# BCN3D.net
KiCad netlist of a schematic drawn in EAGLE
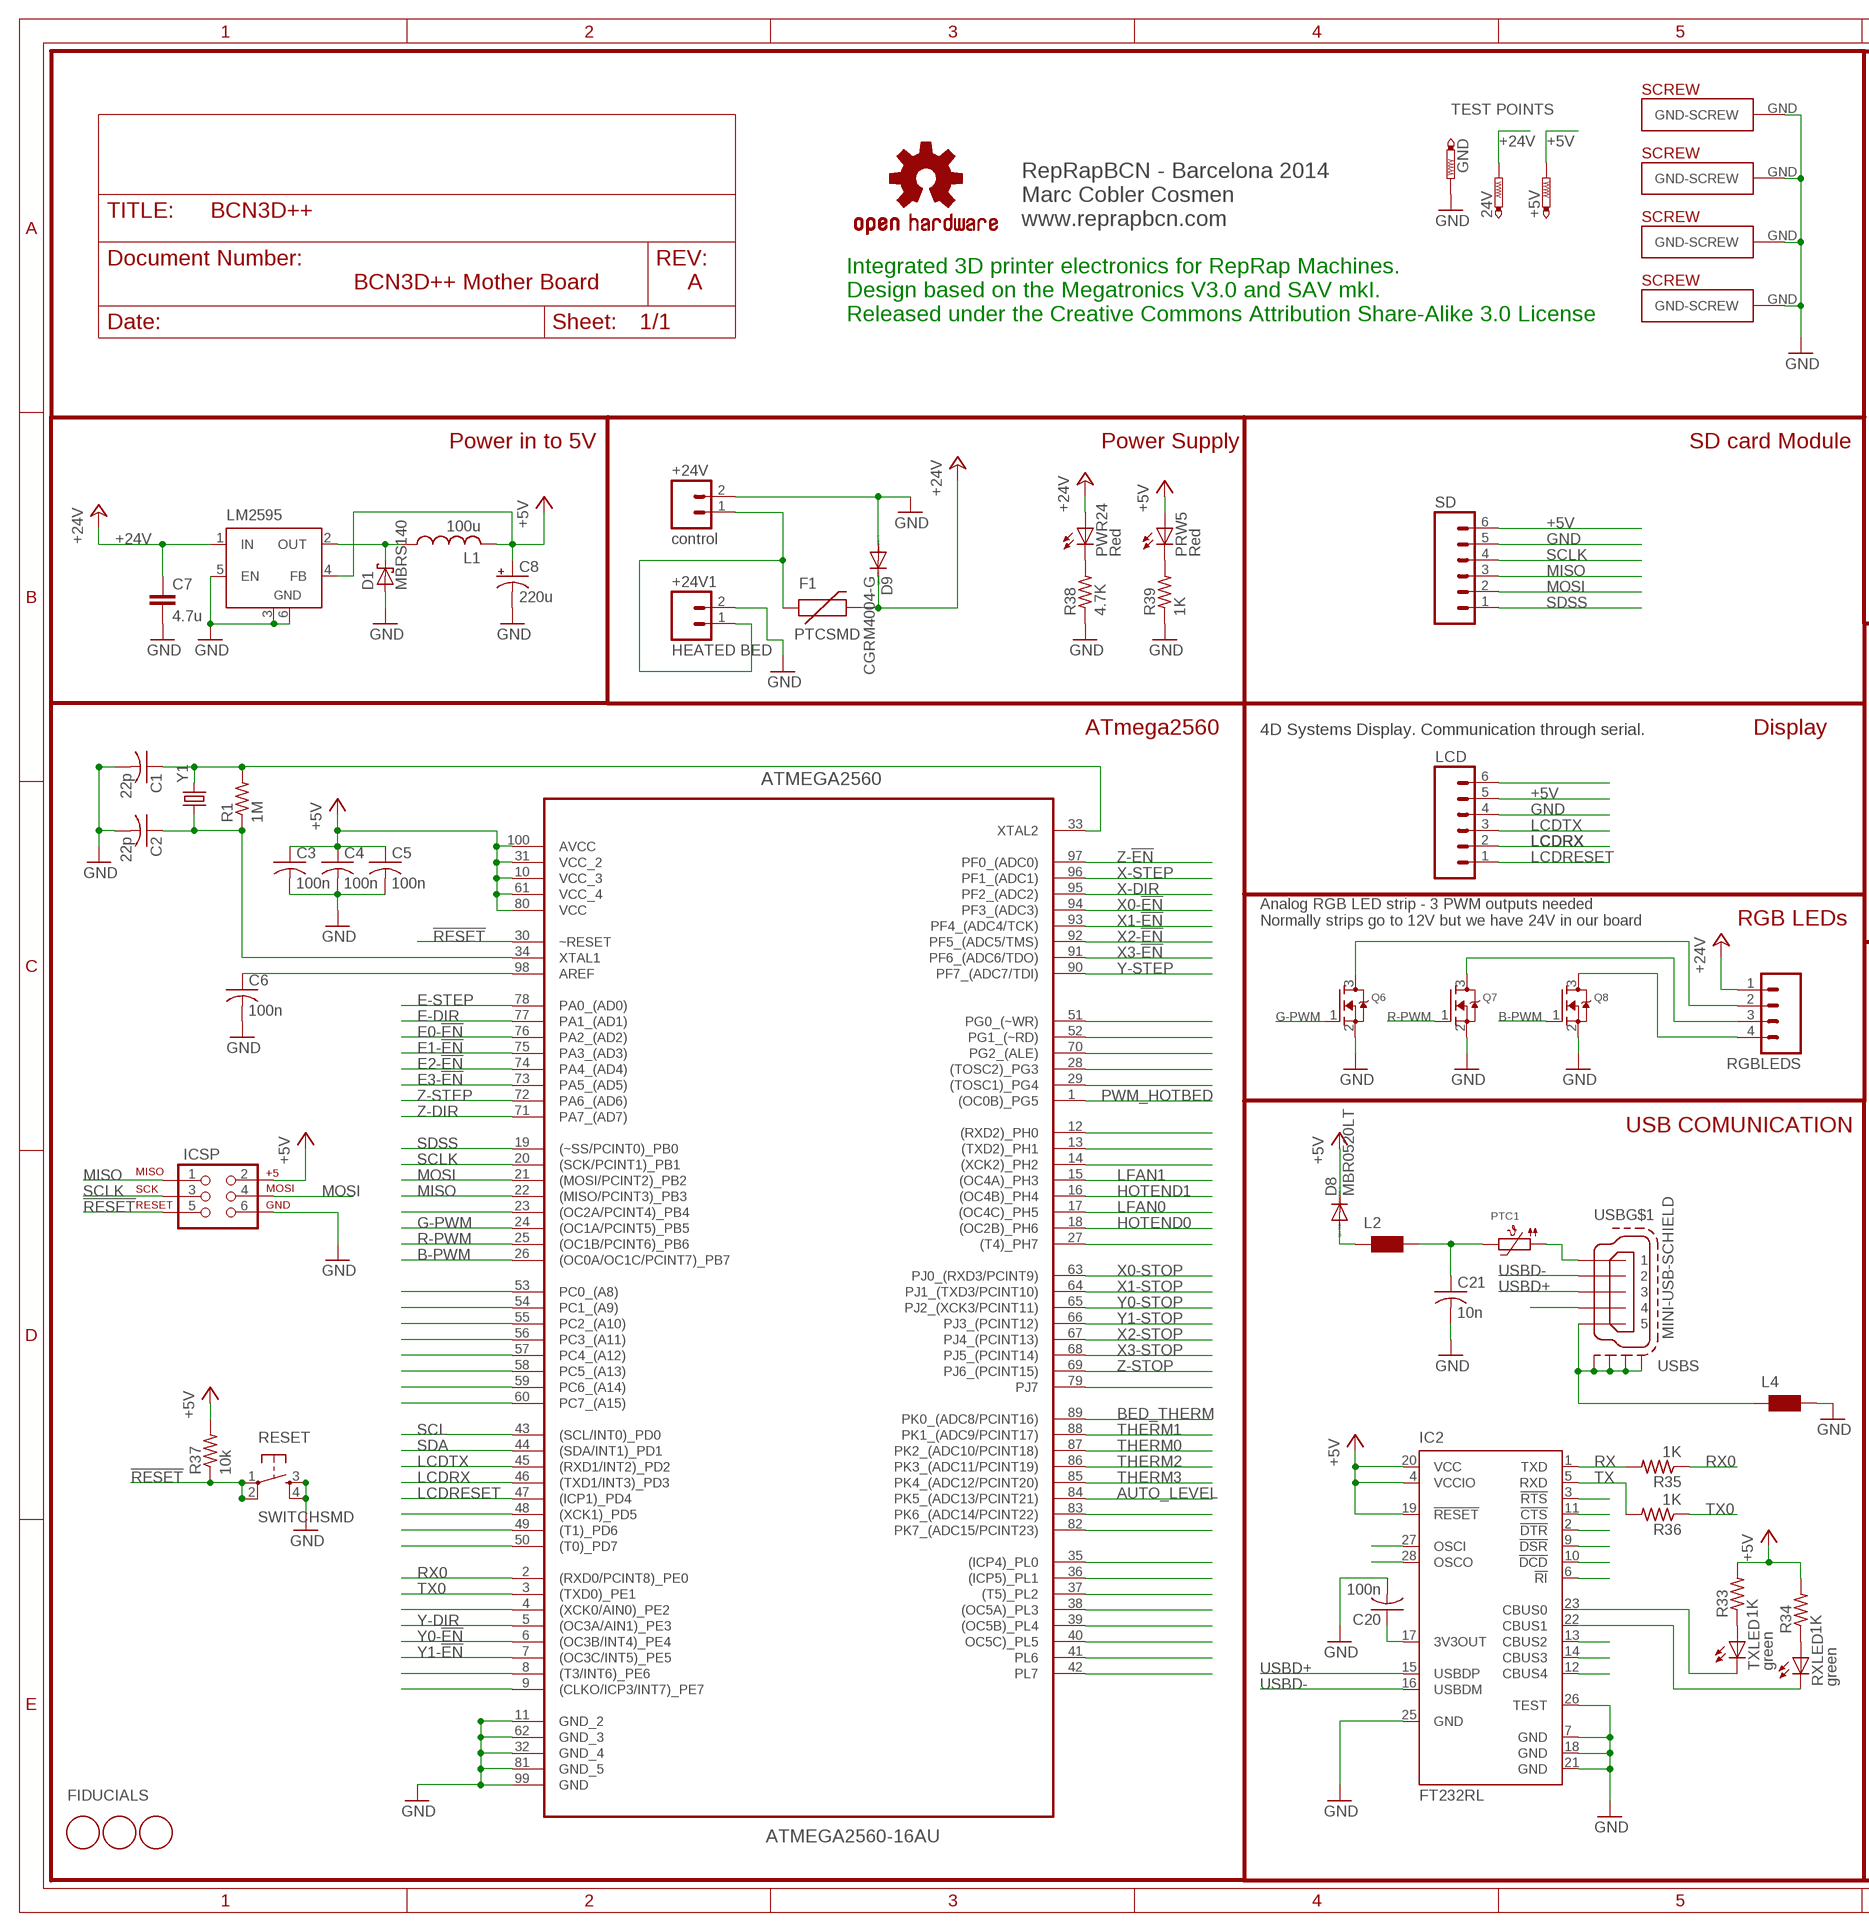
[diagram p0: schematic, sheet 1, part 1 of 2]
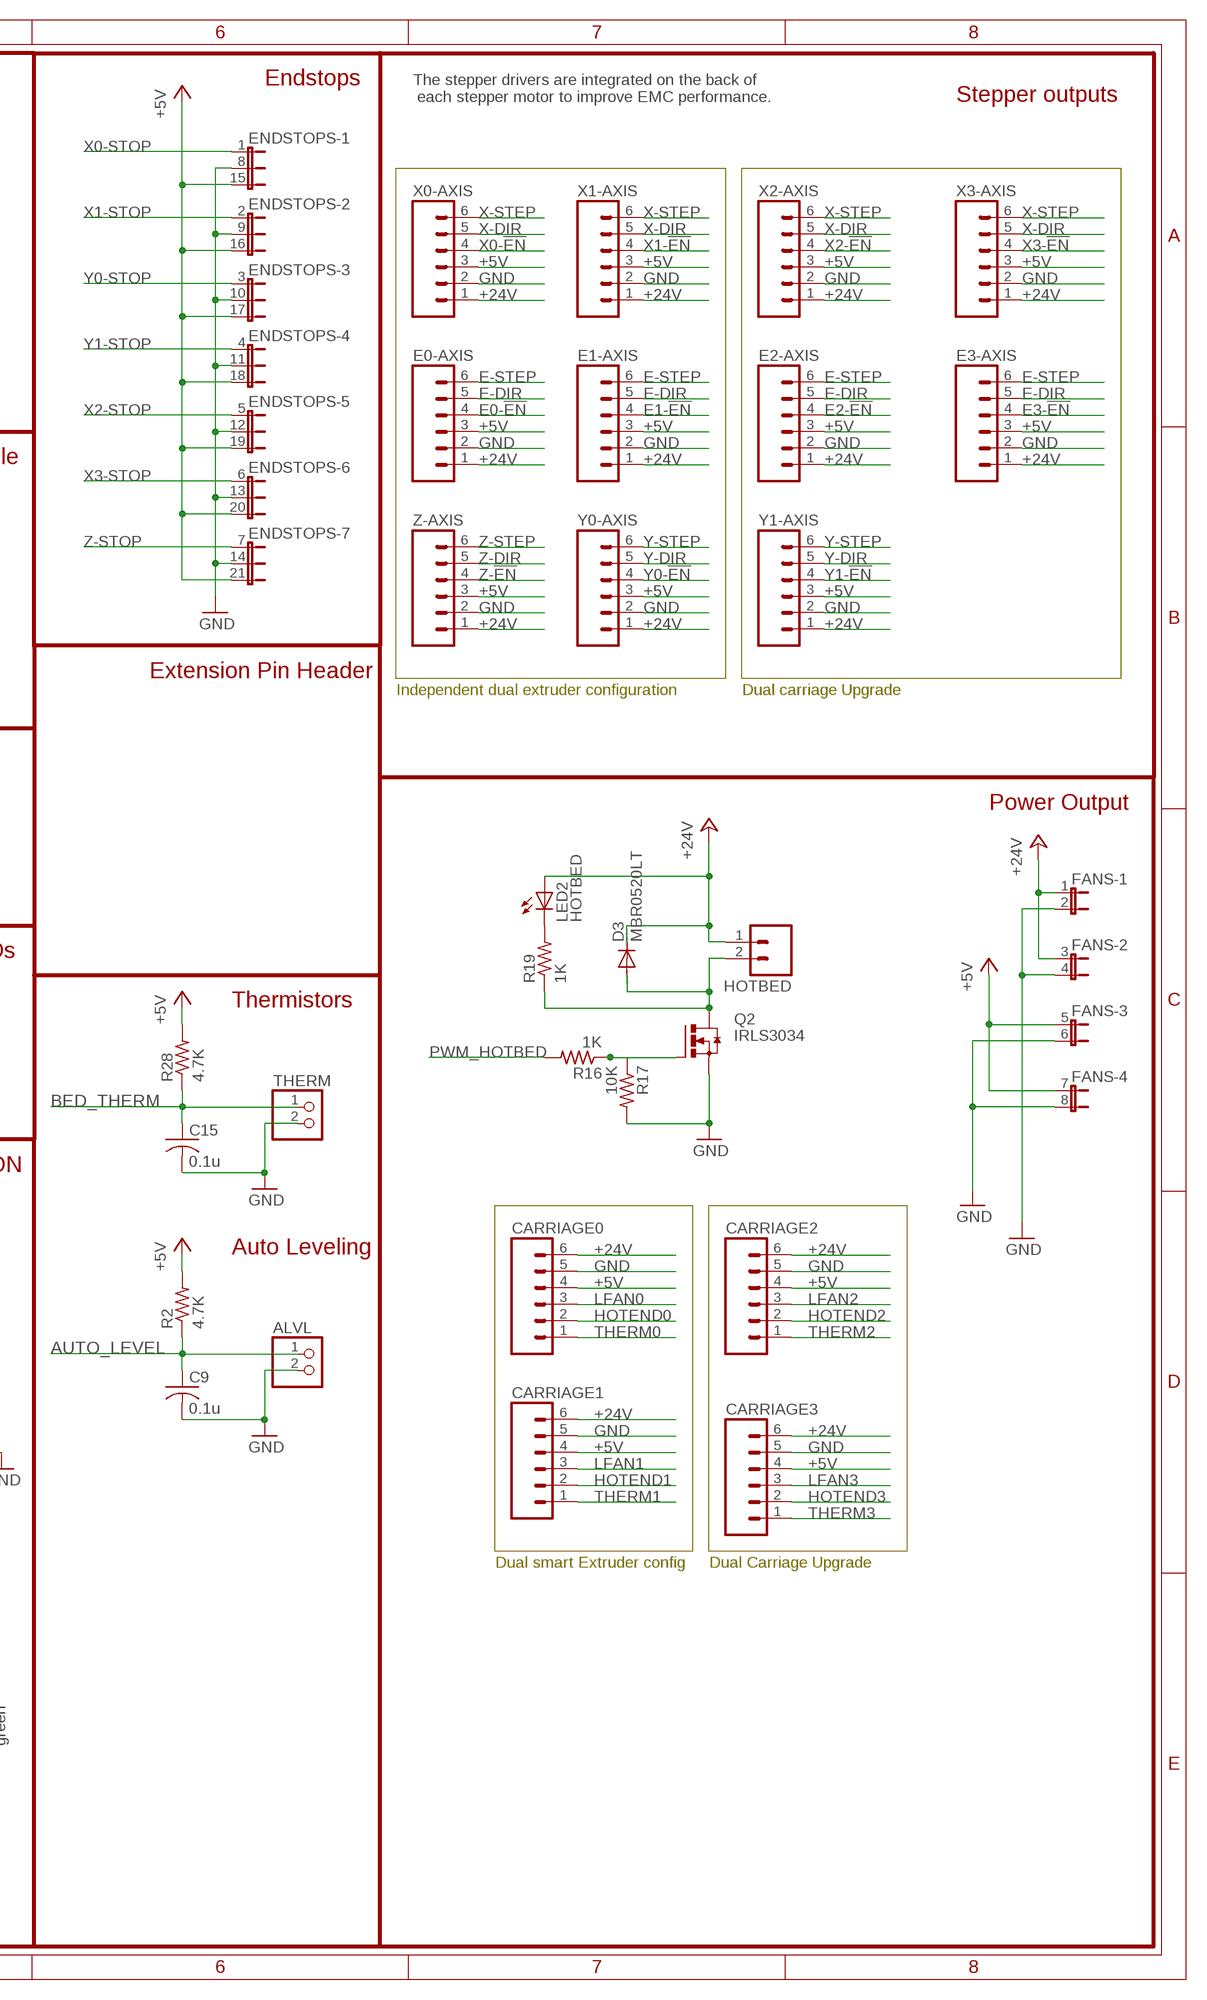
[diagram p1: schematic, sheet 1, part 2 of 2]

(export (version "E")
  (design (tool "Eeschema 10.0.6"))
  (components
    (comp (ref "+5V")
      (value "PTR1TP12SQ")
      (footprint "eagle-import:TP12SQ")
      (libsource (lib "eagle-import") (part "PTR1TP12SQ"))
    )
    (comp (ref "+24V")
      (value "control")
      (footprint "eagle-import:SCREWTERMINAL-5MM-2")
      (libsource (lib "eagle-import") (part "M025MM"))
    )
    (comp (ref "+24V1")
      (value "HEATED BED")
      (footprint "eagle-import:SCREWTERMINAL-5MM-2")
      (libsource (lib "eagle-import") (part "M025MM"))
    )
    (comp (ref "24V")
      (value "PTR1TP12SQ")
      (footprint "eagle-import:TP12SQ")
      (libsource (lib "eagle-import") (part "PTR1TP12SQ"))
    )
    (comp (ref "ALVL")
      (value "PINHD-1X2")
      (footprint "eagle-import:1X02")
      (libsource (lib "eagle-import") (part "PINHD-1X2"))
    )
    (comp (ref "ATMEGA2560")
      (value "ATMEGA2560-16AU")
      (footprint "eagle-import:QFP50P1600X1600X120-100N")
      (libsource (lib "eagle-import") (part "ATMEGA2560-16AU"))
    )
    (comp (ref "C1")
      (value "22p")
      (footprint "eagle-import:C0805")
      (libsource (lib "eagle-import") (part "resistor_C-USC0805"))
    )
    (comp (ref "C2")
      (value "22p")
      (footprint "eagle-import:C0805")
      (libsource (lib "eagle-import") (part "resistor_C-USC0805"))
    )
    (comp (ref "C3")
      (value "100n")
      (footprint "eagle-import:C0805")
      (libsource (lib "eagle-import") (part "rcl_C-USC0805"))
    )
    (comp (ref "C4")
      (value "100n")
      (footprint "eagle-import:C0805")
      (libsource (lib "eagle-import") (part "rcl_C-USC0805"))
    )
    (comp (ref "C5")
      (value "100n")
      (footprint "eagle-import:C0805")
      (libsource (lib "eagle-import") (part "rcl_C-USC0805"))
    )
    (comp (ref "C6")
      (value "100n")
      (footprint "eagle-import:C0805")
      (libsource (lib "eagle-import") (part "rcl_C-USC0805"))
    )
    (comp (ref "C7")
      (value "4.7u")
      (footprint "eagle-import:C1206K")
      (libsource (lib "eagle-import") (part "C-EUC1206K"))
    )
    (comp (ref "C8")
      (value "220u")
      (footprint "eagle-import:UD-8X10_NICHICON")
      (libsource (lib "eagle-import") (part "CPOL-USUD-8X10"))
    )
    (comp (ref "C9")
      (value "0.1u")
      (footprint "eagle-import:C0805")
      (libsource (lib "eagle-import") (part "rcl_C-USC0805"))
    )
    (comp (ref "C15")
      (value "0.1u")
      (footprint "eagle-import:C0805")
      (libsource (lib "eagle-import") (part "rcl_C-USC0805"))
    )
    (comp (ref "C20")
      (value "100n")
      (footprint "eagle-import:C0805")
      (libsource (lib "eagle-import") (part "rcl_C-USC0805"))
    )
    (comp (ref "C21")
      (value "10n")
      (footprint "eagle-import:C0805K")
      (libsource (lib "eagle-import") (part "C-USC0805K"))
    )
    (comp (ref "CARRIAGE0")
      (value "M06SIP")
      (footprint "eagle-import:1X06")
      (libsource (lib "eagle-import") (part "M06SIP"))
    )
    (comp (ref "CARRIAGE1")
      (value "M06SIP")
      (footprint "eagle-import:1X06")
      (libsource (lib "eagle-import") (part "M06SIP"))
    )
    (comp (ref "CARRIAGE2")
      (value "M06SIP")
      (footprint "eagle-import:1X06")
      (libsource (lib "eagle-import") (part "M06SIP"))
    )
    (comp (ref "CARRIAGE3")
      (value "M06SIP")
      (footprint "eagle-import:1X06")
      (libsource (lib "eagle-import") (part "M06SIP"))
    )
    (comp (ref "D1")
      (value "MBRS140")
      (footprint "eagle-import:DO-214AA")
      (libsource (lib "eagle-import") (part "SHOTTKY-DIODESMBRS140"))
    )
    (comp (ref "D3")
      (value "MBR0520LT")
      (footprint "eagle-import:SOD123")
      (libsource (lib "eagle-import") (part "MBR0520LT"))
    )
    (comp (ref "D8")
      (value "MBR0520LT")
      (footprint "eagle-import:SOD123")
      (libsource (lib "eagle-import") (part "MBR0520LT"))
    )
    (comp (ref "D9")
      (value "CGRM4004-G")
      (footprint "eagle-import:SOD-123_MINI-SMA")
      (libsource (lib "eagle-import") (part "CGRM400-G4"))
    )
    (comp (ref "E0-AXIS")
      (value "M06SIP")
      (footprint "eagle-import:1X06")
      (libsource (lib "eagle-import") (part "M06SIP"))
    )
    (comp (ref "E1-AXIS")
      (value "M06SIP")
      (footprint "eagle-import:1X06")
      (libsource (lib "eagle-import") (part "M06SIP"))
    )
    (comp (ref "E2-AXIS")
      (value "M06SIP")
      (footprint "eagle-import:1X06")
      (libsource (lib "eagle-import") (part "M06SIP"))
    )
    (comp (ref "E3-AXIS")
      (value "M06SIP")
      (footprint "eagle-import:1X06")
      (libsource (lib "eagle-import") (part "M06SIP"))
    )
    (comp (ref "ENDSTOPS")
      (value "PINCONNECTOR-7X3")
      (footprint "eagle-import:MALE-PIN-3X7")
      (libsource (lib "eagle-import") (part "PINCONNECTOR-7X3"))
    )
    (comp (ref "F1")
      (value "PTCSMD")
      (footprint "eagle-import:PTC-1206")
      (libsource (lib "eagle-import") (part "PTCSMD"))
    )
    (comp (ref "FANS")
      (value "JP4QE")
      (footprint "eagle-import:JP4Q")
      (libsource (lib "eagle-import") (part "JP4QE"))
    )
    (comp (ref "FID1")
      (value "FIDUCIAL")
      (footprint "eagle-import:FIDUCIAL_1MM")
      (libsource (lib "eagle-import") (part "FIDUCIAL"))
    )
    (comp (ref "FID2")
      (value "FIDUCIAL")
      (footprint "eagle-import:FIDUCIAL_1MM")
      (libsource (lib "eagle-import") (part "FIDUCIAL"))
    )
    (comp (ref "FID3")
      (value "FIDUCIAL")
      (footprint "eagle-import:FIDUCIAL_1MM")
      (libsource (lib "eagle-import") (part "FIDUCIAL"))
    )
    (comp (ref "GND")
      (value "PTR1TP12SQ")
      (footprint "eagle-import:TP12SQ")
      (libsource (lib "eagle-import") (part "PTR1TP12SQ"))
    )
    (comp (ref "HOTBED")
      (value "M025MM")
      (footprint "eagle-import:SCREWTERMINAL-5MM-2")
      (libsource (lib "eagle-import") (part "M025MM"))
    )
    (comp (ref "IC2")
      (value "FT232RL")
      (footprint "eagle-import:SSOP28")
      (libsource (lib "eagle-import") (part "FT232RL"))
    )
    (comp (ref "ICSP")
      (value "AVR_SPI_PRG_6NS")
      (footprint "eagle-import:2X3-NS")
      (libsource (lib "eagle-import") (part "AVR_SPI_PRG_6NS"))
    )
    (comp (ref "L1")
      (value "100u")
      (footprint "eagle-import:SSR1260")
      (libsource (lib "eagle-import") (part "INDUCTANCE"))
    )
    (comp (ref "L2")
      (value "WUERTH-ELEKTRONIK_WE-CBF_1206W")
      (footprint "eagle-import:WUERTH-ELEKTRONIK_1206W")
      (libsource (lib "eagle-import") (part "WUERTH-ELEKTRONIK_WE-CBF_1206W"))
    )
    (comp (ref "L4")
      (value "WUERTH-ELEKTRONIK_WE-CBF_1206W")
      (footprint "eagle-import:WUERTH-ELEKTRONIK_1206W")
      (libsource (lib "eagle-import") (part "WUERTH-ELEKTRONIK_WE-CBF_1206W"))
    )
    (comp (ref "LCD")
      (value "M06SIP")
      (footprint "eagle-import:1X06")
      (libsource (lib "eagle-import") (part "M06SIP"))
    )
    (comp (ref "LED2")
      (value "HOTBED")
      (footprint "eagle-import:CHIP-LED0603")
      (libsource (lib "eagle-import") (part "LEDCHIP-LED0603"))
    )
    (comp (ref "LM2595")
      (value "LM2596S")
      (footprint "eagle-import:TO263-5")
      (libsource (lib "eagle-import") (part "LM2596S"))
    )
    (comp (ref "LOGO1")
      (value "OSHW-LOGOM")
      (footprint "eagle-import:OSHW-LOGO-M")
      (libsource (lib "eagle-import") (part "OSHW-LOGOM"))
    )
    (comp (ref "PRW5")
      (value "Red")
      (footprint "eagle-import:CHIP-LED0805")
      (libsource (lib "eagle-import") (part "LEDCHIP-LED0805"))
    )
    (comp (ref "PTC1")
      (value "MICROBUILDER_PTC1206_L")
      (footprint "eagle-import:MICROBUILDER_1206_PTC")
      (libsource (lib "eagle-import") (part "MICROBUILDER_PTC1206_L"))
    )
    (comp (ref "PWR24")
      (value "Red")
      (footprint "eagle-import:CHIP-LED0805")
      (libsource (lib "eagle-import") (part "LEDCHIP-LED0805"))
    )
    (comp (ref "Q2")
      (value "IRLS3034")
      (footprint "eagle-import:D2PACK")
      (libsource (lib "eagle-import") (part "IRF3704S"))
    )
    (comp (ref "Q6")
      (value "MOSFET-NREFLOW")
      (footprint "eagle-import:SOT23")
      (libsource (lib "eagle-import") (part "MOSFET-NREFLOW"))
    )
    (comp (ref "Q7")
      (value "MOSFET-NREFLOW")
      (footprint "eagle-import:SOT23")
      (libsource (lib "eagle-import") (part "MOSFET-NREFLOW"))
    )
    (comp (ref "Q8")
      (value "MOSFET-NREFLOW")
      (footprint "eagle-import:SOT23")
      (libsource (lib "eagle-import") (part "MOSFET-NREFLOW"))
    )
    (comp (ref "R1")
      (value "1M")
      (footprint "eagle-import:R0805")
      (libsource (lib "eagle-import") (part "resistor_R-US_R0805"))
    )
    (comp (ref "R2")
      (value "4.7K")
      (footprint "eagle-import:M0805")
      (libsource (lib "eagle-import") (part "rcl_R-US_M0805"))
    )
    (comp (ref "R16")
      (value "1K")
      (footprint "eagle-import:M0805")
      (libsource (lib "eagle-import") (part "rcl_R-US_M0805"))
    )
    (comp (ref "R17")
      (value "10K")
      (footprint "eagle-import:M0805")
      (libsource (lib "eagle-import") (part "rcl_R-US_M0805"))
    )
    (comp (ref "R19")
      (value "1K")
      (footprint "eagle-import:M0805")
      (libsource (lib "eagle-import") (part "rcl_R-US_M0805"))
    )
    (comp (ref "R28")
      (value "4.7K")
      (footprint "eagle-import:M0805")
      (libsource (lib "eagle-import") (part "rcl_R-US_M0805"))
    )
    (comp (ref "R33")
      (value "1K")
      (footprint "eagle-import:M0805")
      (libsource (lib "eagle-import") (part "rcl_R-US_M0805"))
    )
    (comp (ref "R34")
      (value "1K")
      (footprint "eagle-import:M0805")
      (libsource (lib "eagle-import") (part "rcl_R-US_M0805"))
    )
    (comp (ref "R35")
      (value "1K")
      (footprint "eagle-import:M0805")
      (libsource (lib "eagle-import") (part "rcl_R-US_M0805"))
    )
    (comp (ref "R36")
      (value "1K")
      (footprint "eagle-import:M0805")
      (libsource (lib "eagle-import") (part "rcl_R-US_M0805"))
    )
    (comp (ref "R37")
      (value "10k")
      (footprint "eagle-import:M0805")
      (libsource (lib "eagle-import") (part "R-US_M0805"))
    )
    (comp (ref "R38")
      (value "4.7K")
      (footprint "eagle-import:R0805")
      (libsource (lib "eagle-import") (part "rcl_R-US_R0805"))
    )
    (comp (ref "R39")
      (value "1K")
      (footprint "eagle-import:R0805")
      (libsource (lib "eagle-import") (part "rcl_R-US_R0805"))
    )
    (comp (ref "RESET")
      (value "SWITCHSMD")
      (footprint "eagle-import:TACTILE-SWITCH-SMD")
      (libsource (lib "eagle-import") (part "TAC_SWITCHSMD"))
    )
    (comp (ref "RGBLEDS")
      (value "M04PTH")
      (footprint "eagle-import:1X04")
      (libsource (lib "eagle-import") (part "M04PTH"))
    )
    (comp (ref "RXLED")
      (value "green")
      (footprint "eagle-import:CHIP-LED0603")
      (libsource (lib "eagle-import") (part "LEDCHIP-LED0603"))
    )
    (comp (ref "SD")
      (value "M06SIP")
      (footprint "eagle-import:1X06")
      (libsource (lib "eagle-import") (part "M06SIP"))
    )
    (comp (ref "THERM")
      (value "PINHD-1X2")
      (footprint "eagle-import:1X02")
      (libsource (lib "eagle-import") (part "PINHD-1X2"))
    )
    (comp (ref "TXLED")
      (value "green")
      (footprint "eagle-import:CHIP-LED0603")
      (libsource (lib "eagle-import") (part "LEDCHIP-LED0603"))
    )
    (comp (ref "U$1")
      (value "SANGUINOLOLU_PLATED-SCREW")
      (footprint "eagle-import:SANGUINOLOLU_PLATEDSCREW")
      (libsource (lib "eagle-import") (part "SANGUINOLOLU_PLATED-SCREW"))
    )
    (comp (ref "U$2")
      (value "SANGUINOLOLU_PLATED-SCREW")
      (footprint "eagle-import:SANGUINOLOLU_PLATEDSCREW")
      (libsource (lib "eagle-import") (part "SANGUINOLOLU_PLATED-SCREW"))
    )
    (comp (ref "U$3")
      (value "SANGUINOLOLU_PLATED-SCREW")
      (footprint "eagle-import:SANGUINOLOLU_PLATEDSCREW")
      (libsource (lib "eagle-import") (part "SANGUINOLOLU_PLATED-SCREW"))
    )
    (comp (ref "U$4")
      (value "SANGUINOLOLU_PLATED-SCREW")
      (footprint "eagle-import:SANGUINOLOLU_PLATEDSCREW")
      (libsource (lib "eagle-import") (part "SANGUINOLOLU_PLATED-SCREW"))
    )
    (comp (ref "USB")
      (value "MINI-USB-SCHIELD")
      (footprint "eagle-import:32005-201")
      (libsource (lib "eagle-import") (part "MINI-USB-SCHIELD-32005-201"))
    )
    (comp (ref "X0-AXIS")
      (value "M06SIP")
      (footprint "eagle-import:1X06")
      (libsource (lib "eagle-import") (part "M06SIP"))
    )
    (comp (ref "X1-AXIS")
      (value "M06SIP")
      (footprint "eagle-import:1X06")
      (libsource (lib "eagle-import") (part "M06SIP"))
    )
    (comp (ref "X2-AXIS")
      (value "M06SIP")
      (footprint "eagle-import:1X06")
      (libsource (lib "eagle-import") (part "M06SIP"))
    )
    (comp (ref "X3-AXIS")
      (value "M06SIP")
      (footprint "eagle-import:1X06")
      (libsource (lib "eagle-import") (part "M06SIP"))
    )
    (comp (ref "Y0-AXIS")
      (value "M06SIP")
      (footprint "eagle-import:1X06")
      (libsource (lib "eagle-import") (part "M06SIP"))
    )
    (comp (ref "Y1")
      (value "CRYSTALHC49US")
      (footprint "eagle-import:HC49US")
      (libsource (lib "eagle-import") (part "CRYSTALHC49US"))
    )
    (comp (ref "Y1-AXIS")
      (value "M06SIP")
      (footprint "eagle-import:1X06")
      (libsource (lib "eagle-import") (part "M06SIP"))
    )
    (comp (ref "Z-AXIS")
      (value "M06SIP")
      (footprint "eagle-import:1X06")
      (libsource (lib "eagle-import") (part "M06SIP"))
    )
  )
  (nets
    (net (code "1") (name "+5V") (class "Default")
      (node (ref "+5V") (pin "TP") (pinfunction "TP_TP") (pintype "input"))
      (node (ref "ATMEGA2560") (pin "10") (pinfunction "VCC_3_10") (pintype "power_in"))
      (node (ref "ATMEGA2560") (pin "100") (pinfunction "AVCC_100") (pintype "power_in"))
      (node (ref "ATMEGA2560") (pin "31") (pinfunction "VCC_2_31") (pintype "power_in"))
      (node (ref "ATMEGA2560") (pin "61") (pinfunction "VCC_4_61") (pintype "power_in"))
      (node (ref "ATMEGA2560") (pin "80") (pinfunction "VCC_80") (pintype "power_in"))
      (node (ref "C3") (pin "1") (pinfunction "1_1") (pintype "passive"))
      (node (ref "C4") (pin "1") (pinfunction "1_1") (pintype "passive"))
      (node (ref "C5") (pin "1") (pinfunction "1_1") (pintype "passive"))
      (node (ref "C8") (pin "+") (pinfunction "+_+") (pintype "passive"))
      (node (ref "CARRIAGE0") (pin "4") (pinfunction "4_4") (pintype "passive"))
      (node (ref "CARRIAGE1") (pin "4") (pinfunction "4_4") (pintype "passive"))
      (node (ref "CARRIAGE2") (pin "4") (pinfunction "4_4") (pintype "passive"))
      (node (ref "CARRIAGE3") (pin "4") (pinfunction "4_4") (pintype "passive"))
      (node (ref "D8") (pin "C") (pinfunction "C_C") (pintype "passive"))
      (node (ref "E0-AXIS") (pin "3") (pinfunction "3_3") (pintype "passive"))
      (node (ref "E1-AXIS") (pin "3") (pinfunction "3_3") (pintype "passive"))
      (node (ref "E2-AXIS") (pin "3") (pinfunction "3_3") (pintype "passive"))
      (node (ref "E3-AXIS") (pin "3") (pinfunction "3_3") (pintype "passive"))
      (node (ref "ENDSTOPS") (pin "15") (pinfunction "3_15") (pintype "passive"))
      (node (ref "ENDSTOPS") (pin "16") (pinfunction "3_16") (pintype "passive"))
      (node (ref "ENDSTOPS") (pin "17") (pinfunction "3_17") (pintype "passive"))
      (node (ref "ENDSTOPS") (pin "18") (pinfunction "3_18") (pintype "passive"))
      (node (ref "ENDSTOPS") (pin "19") (pinfunction "3_19") (pintype "passive"))
      (node (ref "ENDSTOPS") (pin "20") (pinfunction "3_20") (pintype "passive"))
      (node (ref "ENDSTOPS") (pin "21") (pinfunction "3_21") (pintype "passive"))
      (node (ref "FANS") (pin "5") (pinfunction "1_5") (pintype "passive"))
      (node (ref "FANS") (pin "7") (pinfunction "1_7") (pintype "passive"))
      (node (ref "IC2") (pin "19") (pinfunction "~{RESET}_19") (pintype "input"))
      (node (ref "IC2") (pin "20") (pinfunction "VCC_20") (pintype "power_in"))
      (node (ref "IC2") (pin "4") (pinfunction "VCCIO_4") (pintype "power_in"))
      (node (ref "ICSP") (pin "2") (pinfunction "2_2") (pintype "passive"))
      (node (ref "L1") (pin "B") (pinfunction "2_B") (pintype "passive"))
      (node (ref "LCD") (pin "5") (pinfunction "5_5") (pintype "passive"))
      (node (ref "LM2595") (pin "4") (pinfunction "FB_4") (pintype "input"))
      (node (ref "PRW5") (pin "A") (pinfunction "A_A") (pintype "passive"))
      (node (ref "R2") (pin "2") (pinfunction "2_2") (pintype "passive"))
      (node (ref "R28") (pin "2") (pinfunction "2_2") (pintype "passive"))
      (node (ref "R33") (pin "2") (pinfunction "2_2") (pintype "passive"))
      (node (ref "R34") (pin "2") (pinfunction "2_2") (pintype "passive"))
      (node (ref "R37") (pin "2") (pinfunction "2_2") (pintype "passive"))
      (node (ref "SD") (pin "6") (pinfunction "6_6") (pintype "passive"))
      (node (ref "X0-AXIS") (pin "3") (pinfunction "3_3") (pintype "passive"))
      (node (ref "X1-AXIS") (pin "3") (pinfunction "3_3") (pintype "passive"))
      (node (ref "X2-AXIS") (pin "3") (pinfunction "3_3") (pintype "passive"))
      (node (ref "X3-AXIS") (pin "3") (pinfunction "3_3") (pintype "passive"))
      (node (ref "Y0-AXIS") (pin "3") (pinfunction "3_3") (pintype "passive"))
      (node (ref "Y1-AXIS") (pin "3") (pinfunction "3_3") (pintype "passive"))
      (node (ref "Z-AXIS") (pin "3") (pinfunction "3_3") (pintype "passive"))
    )
    (net (code "2") (name "+24V") (class "Default")
      (node (ref "24V") (pin "TP") (pinfunction "TP_TP") (pintype "input"))
      (node (ref "C7") (pin "1") (pinfunction "1_1") (pintype "passive"))
      (node (ref "CARRIAGE0") (pin "6") (pinfunction "6_6") (pintype "passive"))
      (node (ref "CARRIAGE1") (pin "6") (pinfunction "6_6") (pintype "passive"))
      (node (ref "CARRIAGE2") (pin "6") (pinfunction "6_6") (pintype "passive"))
      (node (ref "CARRIAGE3") (pin "6") (pinfunction "6_6") (pintype "passive"))
      (node (ref "D3") (pin "C") (pinfunction "C_C") (pintype "passive"))
      (node (ref "D9") (pin "C") (pinfunction "C_C") (pintype "passive"))
      (node (ref "E0-AXIS") (pin "1") (pinfunction "1_1") (pintype "passive"))
      (node (ref "E1-AXIS") (pin "1") (pinfunction "1_1") (pintype "passive"))
      (node (ref "E2-AXIS") (pin "1") (pinfunction "1_1") (pintype "passive"))
      (node (ref "E3-AXIS") (pin "1") (pinfunction "1_1") (pintype "passive"))
      (node (ref "F1") (pin "2") (pinfunction "2_2") (pintype "bidirectional"))
      (node (ref "FANS") (pin "1") (pinfunction "1_1") (pintype "passive"))
      (node (ref "FANS") (pin "3") (pinfunction "1_3") (pintype "passive"))
      (node (ref "HOTBED") (pin "1") (pinfunction "1_1") (pintype "passive"))
      (node (ref "LED2") (pin "A") (pinfunction "A_A") (pintype "passive"))
      (node (ref "LM2595") (pin "1") (pinfunction "IN_1") (pintype "input"))
      (node (ref "PWR24") (pin "A") (pinfunction "A_A") (pintype "passive"))
      (node (ref "RGBLEDS") (pin "1") (pinfunction "1_1") (pintype "passive"))
      (node (ref "X0-AXIS") (pin "1") (pinfunction "1_1") (pintype "passive"))
      (node (ref "X1-AXIS") (pin "1") (pinfunction "1_1") (pintype "passive"))
      (node (ref "X2-AXIS") (pin "1") (pinfunction "1_1") (pintype "passive"))
      (node (ref "X3-AXIS") (pin "1") (pinfunction "1_1") (pintype "passive"))
      (node (ref "Y0-AXIS") (pin "1") (pinfunction "1_1") (pintype "passive"))
      (node (ref "Y1-AXIS") (pin "1") (pinfunction "1_1") (pintype "passive"))
      (node (ref "Z-AXIS") (pin "1") (pinfunction "1_1") (pintype "passive"))
    )
    (net (code "3") (name "/AUTO_LEVEL") (class "Default")
      (node (ref "ALVL") (pin "1") (pinfunction "1_1") (pintype "passive"))
      (node (ref "ATMEGA2560") (pin "84") (pinfunction "PK5_(ADC13/PCINT21)_84") (pintype "bidirectional"))
      (node (ref "C9") (pin "1") (pinfunction "1_1") (pintype "passive"))
      (node (ref "R2") (pin "1") (pinfunction "1_1") (pintype "passive"))
    )
    (net (code "4") (name "/B-PWM") (class "Default")
      (node (ref "ATMEGA2560") (pin "26") (pinfunction "(OC0A/OC1C/PCINT7)_PB7_26") (pintype "bidirectional"))
      (node (ref "Q8") (pin "1") (pinfunction "G_1") (pintype "bidirectional"))
    )
    (net (code "5") (name "/BED_THERM") (class "Default")
      (node (ref "ATMEGA2560") (pin "89") (pinfunction "PK0_(ADC8/PCINT16)_89") (pintype "bidirectional"))
      (node (ref "C15") (pin "1") (pinfunction "1_1") (pintype "passive"))
      (node (ref "R28") (pin "1") (pinfunction "1_1") (pintype "passive"))
      (node (ref "THERM") (pin "1") (pinfunction "1_1") (pintype "passive"))
    )
    (net (code "6") (name "/E-DIR") (class "Default")
      (node (ref "ATMEGA2560") (pin "77") (pinfunction "PA1_(AD1)_77") (pintype "bidirectional"))
      (node (ref "E0-AXIS") (pin "5") (pinfunction "5_5") (pintype "passive"))
      (node (ref "E1-AXIS") (pin "5") (pinfunction "5_5") (pintype "passive"))
      (node (ref "E2-AXIS") (pin "5") (pinfunction "5_5") (pintype "passive"))
      (node (ref "E3-AXIS") (pin "5") (pinfunction "5_5") (pintype "passive"))
    )
    (net (code "7") (name "/E-STEP") (class "Default")
      (node (ref "ATMEGA2560") (pin "78") (pinfunction "PA0_(AD0)_78") (pintype "bidirectional"))
      (node (ref "E0-AXIS") (pin "6") (pinfunction "6_6") (pintype "passive"))
      (node (ref "E1-AXIS") (pin "6") (pinfunction "6_6") (pintype "passive"))
      (node (ref "E2-AXIS") (pin "6") (pinfunction "6_6") (pintype "passive"))
      (node (ref "E3-AXIS") (pin "6") (pinfunction "6_6") (pintype "passive"))
    )
    (net (code "8") (name "/E0-~{EN}") (class "Default")
      (node (ref "ATMEGA2560") (pin "76") (pinfunction "PA2_(AD2)_76") (pintype "bidirectional"))
      (node (ref "E0-AXIS") (pin "4") (pinfunction "4_4") (pintype "passive"))
    )
    (net (code "9") (name "/E1-~{EN}") (class "Default")
      (node (ref "ATMEGA2560") (pin "75") (pinfunction "PA3_(AD3)_75") (pintype "bidirectional"))
      (node (ref "E1-AXIS") (pin "4") (pinfunction "4_4") (pintype "passive"))
    )
    (net (code "10") (name "/E2-~{EN}") (class "Default")
      (node (ref "ATMEGA2560") (pin "74") (pinfunction "PA4_(AD4)_74") (pintype "bidirectional"))
      (node (ref "E2-AXIS") (pin "4") (pinfunction "4_4") (pintype "passive"))
    )
    (net (code "11") (name "/E3-~{EN}") (class "Default")
      (node (ref "ATMEGA2560") (pin "73") (pinfunction "PA5_(AD5)_73") (pintype "bidirectional"))
      (node (ref "E3-AXIS") (pin "4") (pinfunction "4_4") (pintype "passive"))
    )
    (net (code "12") (name "/G-PWM") (class "Default")
      (node (ref "ATMEGA2560") (pin "24") (pinfunction "(OC1A/PCINT5)_PB5_24") (pintype "bidirectional"))
      (node (ref "Q6") (pin "1") (pinfunction "G_1") (pintype "bidirectional"))
    )
    (net (code "13") (name "/HOTEND0") (class "Default")
      (node (ref "ATMEGA2560") (pin "18") (pinfunction "(OC2B)_PH6_18") (pintype "bidirectional"))
      (node (ref "CARRIAGE0") (pin "2") (pinfunction "2_2") (pintype "passive"))
    )
    (net (code "14") (name "/HOTEND1") (class "Default")
      (node (ref "ATMEGA2560") (pin "16") (pinfunction "(OC4B)_PH4_16") (pintype "bidirectional"))
      (node (ref "CARRIAGE1") (pin "2") (pinfunction "2_2") (pintype "passive"))
    )
    (net (code "15") (name "/HOTEND2") (class "Default")
      (node (ref "CARRIAGE2") (pin "2") (pinfunction "2_2") (pintype "passive"))
    )
    (net (code "16") (name "/HOTEND3") (class "Default")
      (node (ref "CARRIAGE3") (pin "2") (pinfunction "2_2") (pintype "passive"))
    )
    (net (code "17") (name "/LCDRESET") (class "Default")
      (node (ref "ATMEGA2560") (pin "47") (pinfunction "(ICP1)_PD4_47") (pintype "bidirectional"))
      (node (ref "LCD") (pin "1") (pinfunction "1_1") (pintype "passive"))
    )
    (net (code "18") (name "/LCDRX") (class "Default")
      (node (ref "ATMEGA2560") (pin "46") (pinfunction "(TXD1/INT3)_PD3_46") (pintype "bidirectional"))
      (node (ref "LCD") (pin "2") (pinfunction "2_2") (pintype "passive"))
    )
    (net (code "19") (name "/LCDTX") (class "Default")
      (node (ref "ATMEGA2560") (pin "45") (pinfunction "(RXD1/INT2)_PD2_45") (pintype "bidirectional"))
      (node (ref "LCD") (pin "3") (pinfunction "3_3") (pintype "passive"))
    )
    (net (code "20") (name "/LFAN0") (class "Default")
      (node (ref "ATMEGA2560") (pin "17") (pinfunction "(OC4C)_PH5_17") (pintype "bidirectional"))
      (node (ref "CARRIAGE0") (pin "3") (pinfunction "3_3") (pintype "passive"))
    )
    (net (code "21") (name "/LFAN1") (class "Default")
      (node (ref "ATMEGA2560") (pin "15") (pinfunction "(OC4A)_PH3_15") (pintype "bidirectional"))
      (node (ref "CARRIAGE1") (pin "3") (pinfunction "3_3") (pintype "passive"))
    )
    (net (code "22") (name "/LFAN2") (class "Default")
      (node (ref "CARRIAGE2") (pin "3") (pinfunction "3_3") (pintype "passive"))
    )
    (net (code "23") (name "/LFAN3") (class "Default")
      (node (ref "CARRIAGE3") (pin "3") (pinfunction "3_3") (pintype "passive"))
    )
    (net (code "24") (name "/MISO") (class "Default")
      (node (ref "ATMEGA2560") (pin "22") (pinfunction "(MISO/PCINT3)_PB3_22") (pintype "bidirectional"))
      (node (ref "ICSP") (pin "1") (pinfunction "1_1") (pintype "passive"))
      (node (ref "SD") (pin "3") (pinfunction "3_3") (pintype "passive"))
    )
    (net (code "25") (name "/MOSI") (class "Default")
      (node (ref "ATMEGA2560") (pin "21") (pinfunction "(MOSI/PCINT2)_PB2_21") (pintype "bidirectional"))
      (node (ref "ICSP") (pin "4") (pinfunction "4_4") (pintype "passive"))
      (node (ref "SD") (pin "2") (pinfunction "2_2") (pintype "passive"))
    )
    (net (code "26") (name "/PWM_HOTBED") (class "Default")
      (node (ref "ATMEGA2560") (pin "1") (pinfunction "(OC0B)_PG5_1") (pintype "bidirectional"))
      (node (ref "R16") (pin "2") (pinfunction "2_2") (pintype "passive"))
    )
    (net (code "27") (name "/R-PWM") (class "Default")
      (node (ref "ATMEGA2560") (pin "25") (pinfunction "(OC1B/PCINT6)_PB6_25") (pintype "bidirectional"))
      (node (ref "Q7") (pin "1") (pinfunction "G_1") (pintype "bidirectional"))
    )
    (net (code "28") (name "/RX") (class "Default")
      (node (ref "IC2") (pin "1") (pinfunction "TXD_1") (pintype "output"))
      (node (ref "R35") (pin "2") (pinfunction "2_2") (pintype "passive"))
    )
    (net (code "29") (name "/RX0") (class "Default")
      (node (ref "ATMEGA2560") (pin "2") (pinfunction "(RXD0/PCINT8)_PE0_2") (pintype "bidirectional"))
      (node (ref "R35") (pin "1") (pinfunction "1_1") (pintype "passive"))
    )
    (net (code "30") (name "/SCL") (class "Default")
      (node (ref "ATMEGA2560") (pin "43") (pinfunction "(SCL/INT0)_PD0_43") (pintype "bidirectional"))
    )
    (net (code "31") (name "/SCLK") (class "Default")
      (node (ref "ATMEGA2560") (pin "20") (pinfunction "(SCK/PCINT1)_PB1_20") (pintype "bidirectional"))
      (node (ref "ICSP") (pin "3") (pinfunction "3_3") (pintype "passive"))
      (node (ref "SD") (pin "4") (pinfunction "4_4") (pintype "passive"))
    )
    (net (code "32") (name "/SDA") (class "Default")
      (node (ref "ATMEGA2560") (pin "44") (pinfunction "(SDA/INT1)_PD1_44") (pintype "bidirectional"))
    )
    (net (code "33") (name "/SDSS") (class "Default")
      (node (ref "ATMEGA2560") (pin "19") (pinfunction "(~{SS/PCINT0})_PB0_19") (pintype "bidirectional"))
      (node (ref "SD") (pin "1") (pinfunction "1_1") (pintype "passive"))
    )
    (net (code "34") (name "/THERM0") (class "Default")
      (node (ref "ATMEGA2560") (pin "87") (pinfunction "PK2_(ADC10/PCINT18)_87") (pintype "bidirectional"))
      (node (ref "CARRIAGE0") (pin "1") (pinfunction "1_1") (pintype "passive"))
    )
    (net (code "35") (name "/THERM1") (class "Default")
      (node (ref "ATMEGA2560") (pin "88") (pinfunction "PK1_(ADC9/PCINT17)_88") (pintype "bidirectional"))
      (node (ref "CARRIAGE1") (pin "1") (pinfunction "1_1") (pintype "passive"))
    )
    (net (code "36") (name "/THERM2") (class "Default")
      (node (ref "ATMEGA2560") (pin "86") (pinfunction "PK3_(ADC11/PCINT19)_86") (pintype "bidirectional"))
      (node (ref "CARRIAGE2") (pin "1") (pinfunction "1_1") (pintype "passive"))
    )
    (net (code "37") (name "/THERM3") (class "Default")
      (node (ref "ATMEGA2560") (pin "85") (pinfunction "PK4_(ADC12/PCINT20)_85") (pintype "bidirectional"))
      (node (ref "CARRIAGE3") (pin "1") (pinfunction "1_1") (pintype "passive"))
    )
    (net (code "38") (name "/TX") (class "Default")
      (node (ref "IC2") (pin "5") (pinfunction "RXD_5") (pintype "input"))
      (node (ref "R36") (pin "2") (pinfunction "2_2") (pintype "passive"))
    )
    (net (code "39") (name "/TX0") (class "Default")
      (node (ref "ATMEGA2560") (pin "3") (pinfunction "(TXD0)_PE1_3") (pintype "bidirectional"))
      (node (ref "R36") (pin "1") (pinfunction "1_1") (pintype "passive"))
    )
    (net (code "40") (name "/USBD+") (class "Default")
      (node (ref "IC2") (pin "15") (pinfunction "USBDP_15") (pintype "bidirectional"))
      (node (ref "USB") (pin "3") (pinfunction "3_3") (pintype "passive"))
    )
    (net (code "41") (name "/USBD-") (class "Default")
      (node (ref "IC2") (pin "16") (pinfunction "USBDM_16") (pintype "bidirectional"))
      (node (ref "USB") (pin "2") (pinfunction "2_2") (pintype "passive"))
    )
    (net (code "42") (name "/X-DIR") (class "Default")
      (node (ref "ATMEGA2560") (pin "95") (pinfunction "PF2_(ADC2)_95") (pintype "bidirectional"))
      (node (ref "X0-AXIS") (pin "5") (pinfunction "5_5") (pintype "passive"))
      (node (ref "X1-AXIS") (pin "5") (pinfunction "5_5") (pintype "passive"))
      (node (ref "X2-AXIS") (pin "5") (pinfunction "5_5") (pintype "passive"))
      (node (ref "X3-AXIS") (pin "5") (pinfunction "5_5") (pintype "passive"))
    )
    (net (code "43") (name "/X-STEP") (class "Default")
      (node (ref "ATMEGA2560") (pin "96") (pinfunction "PF1_(ADC1)_96") (pintype "bidirectional"))
      (node (ref "X0-AXIS") (pin "6") (pinfunction "6_6") (pintype "passive"))
      (node (ref "X1-AXIS") (pin "6") (pinfunction "6_6") (pintype "passive"))
      (node (ref "X2-AXIS") (pin "6") (pinfunction "6_6") (pintype "passive"))
      (node (ref "X3-AXIS") (pin "6") (pinfunction "6_6") (pintype "passive"))
    )
    (net (code "44") (name "/X0-STOP") (class "Default")
      (node (ref "ATMEGA2560") (pin "63") (pinfunction "PJ0_(RXD3/PCINT9)_63") (pintype "bidirectional"))
      (node (ref "ENDSTOPS") (pin "1") (pinfunction "1_1") (pintype "passive"))
    )
    (net (code "45") (name "/X0-~{EN}") (class "Default")
      (node (ref "ATMEGA2560") (pin "94") (pinfunction "PF3_(ADC3)_94") (pintype "bidirectional"))
      (node (ref "X0-AXIS") (pin "4") (pinfunction "4_4") (pintype "passive"))
    )
    (net (code "46") (name "/X1-STOP") (class "Default")
      (node (ref "ATMEGA2560") (pin "64") (pinfunction "PJ1_(TXD3/PCINT10)_64") (pintype "bidirectional"))
      (node (ref "ENDSTOPS") (pin "2") (pinfunction "1_2") (pintype "passive"))
    )
    (net (code "47") (name "/X1-~{EN}") (class "Default")
      (node (ref "ATMEGA2560") (pin "93") (pinfunction "PF4_(ADC4/TCK)_93") (pintype "bidirectional"))
      (node (ref "X1-AXIS") (pin "4") (pinfunction "4_4") (pintype "passive"))
    )
    (net (code "48") (name "/X2-STOP") (class "Default")
      (node (ref "ATMEGA2560") (pin "67") (pinfunction "PJ4_(PCINT13)_67") (pintype "bidirectional"))
      (node (ref "ENDSTOPS") (pin "5") (pinfunction "1_5") (pintype "passive"))
    )
    (net (code "49") (name "/X2-~{EN}") (class "Default")
      (node (ref "ATMEGA2560") (pin "92") (pinfunction "PF5_(ADC5/TMS)_92") (pintype "bidirectional"))
      (node (ref "X2-AXIS") (pin "4") (pinfunction "4_4") (pintype "passive"))
    )
    (net (code "50") (name "/X3-STOP") (class "Default")
      (node (ref "ATMEGA2560") (pin "68") (pinfunction "PJ5_(PCINT14)_68") (pintype "bidirectional"))
      (node (ref "ENDSTOPS") (pin "6") (pinfunction "1_6") (pintype "passive"))
    )
    (net (code "51") (name "/X3-~{EN}") (class "Default")
      (node (ref "ATMEGA2560") (pin "91") (pinfunction "PF6_(ADC6/TDO)_91") (pintype "bidirectional"))
      (node (ref "X3-AXIS") (pin "4") (pinfunction "4_4") (pintype "passive"))
    )
    (net (code "52") (name "/Y-DIR") (class "Default")
      (node (ref "ATMEGA2560") (pin "5") (pinfunction "(OC3A/AIN1)_PE3_5") (pintype "bidirectional"))
      (node (ref "Y0-AXIS") (pin "5") (pinfunction "5_5") (pintype "passive"))
      (node (ref "Y1-AXIS") (pin "5") (pinfunction "5_5") (pintype "passive"))
    )
    (net (code "53") (name "/Y-STEP") (class "Default")
      (node (ref "ATMEGA2560") (pin "90") (pinfunction "PF7_(ADC7/TDI)_90") (pintype "bidirectional"))
      (node (ref "Y0-AXIS") (pin "6") (pinfunction "6_6") (pintype "passive"))
      (node (ref "Y1-AXIS") (pin "6") (pinfunction "6_6") (pintype "passive"))
    )
    (net (code "54") (name "/Y0-STOP") (class "Default")
      (node (ref "ATMEGA2560") (pin "65") (pinfunction "PJ2_(XCK3/PCINT11)_65") (pintype "bidirectional"))
      (node (ref "ENDSTOPS") (pin "3") (pinfunction "1_3") (pintype "passive"))
    )
    (net (code "55") (name "/Y0-~{EN}") (class "Default")
      (node (ref "ATMEGA2560") (pin "6") (pinfunction "(OC3B/INT4)_PE4_6") (pintype "bidirectional"))
      (node (ref "Y0-AXIS") (pin "4") (pinfunction "4_4") (pintype "passive"))
    )
    (net (code "56") (name "/Y1-STOP") (class "Default")
      (node (ref "ATMEGA2560") (pin "66") (pinfunction "PJ3_(PCINT12)_66") (pintype "bidirectional"))
      (node (ref "ENDSTOPS") (pin "4") (pinfunction "1_4") (pintype "passive"))
    )
    (net (code "57") (name "/Y1-~{EN}") (class "Default")
      (node (ref "ATMEGA2560") (pin "7") (pinfunction "(OC3C/INT5)_PE5_7") (pintype "bidirectional"))
      (node (ref "Y1-AXIS") (pin "4") (pinfunction "4_4") (pintype "passive"))
    )
    (net (code "58") (name "/Z-DIR") (class "Default")
      (node (ref "ATMEGA2560") (pin "71") (pinfunction "PA7_(AD7)_71") (pintype "bidirectional"))
      (node (ref "Z-AXIS") (pin "5") (pinfunction "5_5") (pintype "passive"))
    )
    (net (code "59") (name "/Z-STEP") (class "Default")
      (node (ref "ATMEGA2560") (pin "72") (pinfunction "PA6_(AD6)_72") (pintype "bidirectional"))
      (node (ref "Z-AXIS") (pin "6") (pinfunction "6_6") (pintype "passive"))
    )
    (net (code "60") (name "/Z-STOP") (class "Default")
      (node (ref "ATMEGA2560") (pin "69") (pinfunction "PJ6_(PCINT15)_69") (pintype "bidirectional"))
      (node (ref "ENDSTOPS") (pin "7") (pinfunction "1_7") (pintype "passive"))
    )
    (net (code "61") (name "/Z-~{EN}") (class "Default")
      (node (ref "ATMEGA2560") (pin "97") (pinfunction "PF0_(ADC0)_97") (pintype "bidirectional"))
      (node (ref "Z-AXIS") (pin "4") (pinfunction "4_4") (pintype "passive"))
    )
    (net (code "62") (name "/~{RESET}") (class "Default")
      (node (ref "ATMEGA2560") (pin "30") (pinfunction "~{RESET}_30") (pintype "input"))
      (node (ref "ICSP") (pin "5") (pinfunction "5_5") (pintype "passive"))
      (node (ref "R37") (pin "1") (pinfunction "1_1") (pintype "passive"))
      (node (ref "RESET") (pin "1") (pinfunction "1_1") (pintype "passive"))
      (node (ref "RESET") (pin "2") (pinfunction "2_2") (pintype "passive"))
    )
    (net (code "63") (name "GND") (class "Default")
      (node (ref "+24V") (pin "2") (pinfunction "2_2") (pintype "passive"))
      (node (ref "+24V1") (pin "2") (pinfunction "2_2") (pintype "passive"))
      (node (ref "ALVL") (pin "2") (pinfunction "2_2") (pintype "passive"))
      (node (ref "ATMEGA2560") (pin "11") (pinfunction "GND_2_11") (pintype "passive"))
      (node (ref "ATMEGA2560") (pin "32") (pinfunction "GND_4_32") (pintype "passive"))
      (node (ref "ATMEGA2560") (pin "62") (pinfunction "GND_3_62") (pintype "passive"))
      (node (ref "ATMEGA2560") (pin "81") (pinfunction "GND_5_81") (pintype "passive"))
      (node (ref "ATMEGA2560") (pin "99") (pinfunction "GND_99") (pintype "passive"))
      (node (ref "C1") (pin "2") (pinfunction "2_2") (pintype "passive"))
      (node (ref "C15") (pin "2") (pinfunction "2_2") (pintype "passive"))
      (node (ref "C2") (pin "2") (pinfunction "2_2") (pintype "passive"))
      (node (ref "C20") (pin "2") (pinfunction "2_2") (pintype "passive"))
      (node (ref "C21") (pin "2") (pinfunction "2_2") (pintype "passive"))
      (node (ref "C3") (pin "2") (pinfunction "2_2") (pintype "passive"))
      (node (ref "C4") (pin "2") (pinfunction "2_2") (pintype "passive"))
      (node (ref "C5") (pin "2") (pinfunction "2_2") (pintype "passive"))
      (node (ref "C6") (pin "2") (pinfunction "2_2") (pintype "passive"))
      (node (ref "C7") (pin "2") (pinfunction "2_2") (pintype "passive"))
      (node (ref "C8") (pin "-") (pinfunction "-_-") (pintype "passive"))
      (node (ref "C9") (pin "2") (pinfunction "2_2") (pintype "passive"))
      (node (ref "CARRIAGE0") (pin "5") (pinfunction "5_5") (pintype "passive"))
      (node (ref "CARRIAGE1") (pin "5") (pinfunction "5_5") (pintype "passive"))
      (node (ref "CARRIAGE2") (pin "5") (pinfunction "5_5") (pintype "passive"))
      (node (ref "CARRIAGE3") (pin "5") (pinfunction "5_5") (pintype "passive"))
      (node (ref "D1") (pin "A") (pinfunction "A_A") (pintype "passive"))
      (node (ref "D9") (pin "A") (pinfunction "A_A") (pintype "passive"))
      (node (ref "E0-AXIS") (pin "2") (pinfunction "2_2") (pintype "passive"))
      (node (ref "E1-AXIS") (pin "2") (pinfunction "2_2") (pintype "passive"))
      (node (ref "E2-AXIS") (pin "2") (pinfunction "2_2") (pintype "passive"))
      (node (ref "E3-AXIS") (pin "2") (pinfunction "2_2") (pintype "passive"))
      (node (ref "ENDSTOPS") (pin "10") (pinfunction "2_10") (pintype "passive"))
      (node (ref "ENDSTOPS") (pin "11") (pinfunction "2_11") (pintype "passive"))
      (node (ref "ENDSTOPS") (pin "12") (pinfunction "2_12") (pintype "passive"))
      (node (ref "ENDSTOPS") (pin "13") (pinfunction "2_13") (pintype "passive"))
      (node (ref "ENDSTOPS") (pin "14") (pinfunction "2_14") (pintype "passive"))
      (node (ref "ENDSTOPS") (pin "8") (pinfunction "2_8") (pintype "passive"))
      (node (ref "ENDSTOPS") (pin "9") (pinfunction "2_9") (pintype "passive"))
      (node (ref "FANS") (pin "2") (pinfunction "2_2") (pintype "passive"))
      (node (ref "FANS") (pin "4") (pinfunction "2_4") (pintype "passive"))
      (node (ref "FANS") (pin "6") (pinfunction "2_6") (pintype "passive"))
      (node (ref "FANS") (pin "8") (pinfunction "2_8") (pintype "passive"))
      (node (ref "GND") (pin "TP") (pinfunction "TP_TP") (pintype "input"))
      (node (ref "IC2") (pin "18") (pinfunction "GND_18") (pintype "power_in"))
      (node (ref "IC2") (pin "21") (pinfunction "GND_21") (pintype "power_in"))
      (node (ref "IC2") (pin "25") (pinfunction "GND_25") (pintype "power_in"))
      (node (ref "IC2") (pin "26") (pinfunction "TEST_26") (pintype "input"))
      (node (ref "IC2") (pin "7") (pinfunction "GND_7") (pintype "power_in"))
      (node (ref "ICSP") (pin "6") (pinfunction "6_6") (pintype "passive"))
      (node (ref "L4") (pin "2") (pinfunction "2_2") (pintype "passive"))
      (node (ref "LCD") (pin "4") (pinfunction "4_4") (pintype "passive"))
      (node (ref "LM2595") (pin "3") (pinfunction "GND_3") (pintype "power_in"))
      (node (ref "LM2595") (pin "5") (pinfunction "EN_5") (pintype "input"))
      (node (ref "LM2595") (pin "6") (pinfunction "GND_6") (pintype "power_in"))
      (node (ref "Q2") (pin "3") (pinfunction "S_3") (pintype "passive"))
      (node (ref "Q6") (pin "2") (pinfunction "S_2") (pintype "bidirectional"))
      (node (ref "Q7") (pin "2") (pinfunction "S_2") (pintype "bidirectional"))
      (node (ref "Q8") (pin "2") (pinfunction "S_2") (pintype "bidirectional"))
      (node (ref "R17") (pin "2") (pinfunction "2_2") (pintype "passive"))
      (node (ref "R38") (pin "1") (pinfunction "1_1") (pintype "passive"))
      (node (ref "R39") (pin "1") (pinfunction "1_1") (pintype "passive"))
      (node (ref "RESET") (pin "3") (pinfunction "3_3") (pintype "passive"))
      (node (ref "RESET") (pin "4") (pinfunction "4_4") (pintype "passive"))
      (node (ref "SD") (pin "5") (pinfunction "5_5") (pintype "passive"))
      (node (ref "THERM") (pin "2") (pinfunction "2_2") (pintype "passive"))
      (node (ref "U$1") (pin "GND") (pinfunction "GND-SCREW_GND") (pintype "bidirectional"))
      (node (ref "U$2") (pin "GND") (pinfunction "GND-SCREW_GND") (pintype "bidirectional"))
      (node (ref "U$3") (pin "GND") (pinfunction "GND-SCREW_GND") (pintype "bidirectional"))
      (node (ref "U$4") (pin "GND") (pinfunction "GND-SCREW_GND") (pintype "bidirectional"))
      (node (ref "X0-AXIS") (pin "2") (pinfunction "2_2") (pintype "passive"))
      (node (ref "X1-AXIS") (pin "2") (pinfunction "2_2") (pintype "passive"))
      (node (ref "X2-AXIS") (pin "2") (pinfunction "2_2") (pintype "passive"))
      (node (ref "X3-AXIS") (pin "2") (pinfunction "2_2") (pintype "passive"))
      (node (ref "Y0-AXIS") (pin "2") (pinfunction "2_2") (pintype "passive"))
      (node (ref "Y1-AXIS") (pin "2") (pinfunction "2_2") (pintype "passive"))
      (node (ref "Z-AXIS") (pin "2") (pinfunction "2_2") (pintype "passive"))
    )
    (net (code "64") (name "Net-(+24V-Pad1)") (class "Default")
      (node (ref "+24V") (pin "1") (pinfunction "1_1") (pintype "passive"))
      (node (ref "+24V1") (pin "1") (pinfunction "1_1") (pintype "passive"))
      (node (ref "F1") (pin "1") (pinfunction "1_1") (pintype "bidirectional"))
    )
    (net (code "65") (name "Net-(ATMEGA2560-AREF)") (class "Default")
      (node (ref "ATMEGA2560") (pin "98") (pinfunction "AREF_98") (pintype "input"))
      (node (ref "C6") (pin "1") (pinfunction "1_1") (pintype "passive"))
    )
    (net (code "66") (name "Net-(ATMEGA2560-XTAL1)") (class "Default")
      (node (ref "ATMEGA2560") (pin "34") (pinfunction "XTAL1_34") (pintype "input"))
      (node (ref "C2") (pin "1") (pinfunction "1_1") (pintype "passive"))
      (node (ref "R1") (pin "1") (pinfunction "1_1") (pintype "passive"))
      (node (ref "Y1") (pin "1") (pinfunction "1_1") (pintype "passive"))
    )
    (net (code "67") (name "Net-(ATMEGA2560-XTAL2)") (class "Default")
      (node (ref "ATMEGA2560") (pin "33") (pinfunction "XTAL2_33") (pintype "output"))
      (node (ref "C1") (pin "1") (pinfunction "1_1") (pintype "passive"))
      (node (ref "R1") (pin "2") (pinfunction "2_2") (pintype "passive"))
      (node (ref "Y1") (pin "2") (pinfunction "2_2") (pintype "passive"))
    )
    (net (code "68") (name "Net-(C21-Pad1)") (class "Default")
      (node (ref "C21") (pin "1") (pinfunction "1_1") (pintype "passive"))
      (node (ref "L2") (pin "2") (pinfunction "2_2") (pintype "passive"))
      (node (ref "PTC1") (pin "2") (pinfunction "2_2") (pintype "passive"))
    )
    (net (code "69") (name "Net-(D8-PadA)") (class "Default")
      (node (ref "D8") (pin "A") (pinfunction "A_A") (pintype "passive"))
      (node (ref "L2") (pin "1") (pinfunction "1_1") (pintype "passive"))
    )
    (net (code "70") (name "Net-(IC2-3V3OUT)") (class "Default")
      (node (ref "C20") (pin "1") (pinfunction "1_1") (pintype "passive"))
      (node (ref "IC2") (pin "17") (pinfunction "3V3OUT_17") (pintype "output"))
    )
    (net (code "71") (name "Net-(IC2-CBUS0)") (class "Default")
      (node (ref "IC2") (pin "23") (pinfunction "CBUS0_23") (pintype "bidirectional"))
      (node (ref "TXLED") (pin "C") (pinfunction "C_C") (pintype "passive"))
    )
    (net (code "72") (name "Net-(IC2-CBUS1)") (class "Default")
      (node (ref "IC2") (pin "22") (pinfunction "CBUS1_22") (pintype "bidirectional"))
      (node (ref "RXLED") (pin "C") (pinfunction "C_C") (pintype "passive"))
    )
    (net (code "73") (name "Net-(L1-1)") (class "Default")
      (node (ref "D1") (pin "C") (pinfunction "C_C") (pintype "passive"))
      (node (ref "L1") (pin "A") (pinfunction "1_A") (pintype "passive"))
      (node (ref "LM2595") (pin "2") (pinfunction "OUT_2") (pintype "output"))
    )
    (net (code "74") (name "Net-(LED2-PadC)") (class "Default")
      (node (ref "LED2") (pin "C") (pinfunction "C_C") (pintype "passive"))
      (node (ref "R19") (pin "2") (pinfunction "2_2") (pintype "passive"))
    )
    (net (code "75") (name "Net-(PRW5-PadC)") (class "Default")
      (node (ref "PRW5") (pin "C") (pinfunction "C_C") (pintype "passive"))
      (node (ref "R39") (pin "2") (pinfunction "2_2") (pintype "passive"))
    )
    (net (code "76") (name "Net-(PTC1-Pad1)") (class "Default")
      (node (ref "PTC1") (pin "1") (pinfunction "1_1") (pintype "passive"))
      (node (ref "USB") (pin "1") (pinfunction "1_1") (pintype "passive"))
    )
    (net (code "77") (name "Net-(PWR24-PadC)") (class "Default")
      (node (ref "PWR24") (pin "C") (pinfunction "C_C") (pintype "passive"))
      (node (ref "R38") (pin "2") (pinfunction "2_2") (pintype "passive"))
    )
    (net (code "78") (name "Net-(Q2-D)") (class "Default")
      (node (ref "D3") (pin "A") (pinfunction "A_A") (pintype "passive"))
      (node (ref "HOTBED") (pin "2") (pinfunction "2_2") (pintype "passive"))
      (node (ref "Q2") (pin "2") (pinfunction "D_2") (pintype "passive"))
      (node (ref "R19") (pin "1") (pinfunction "1_1") (pintype "passive"))
    )
    (net (code "79") (name "Net-(Q2-G)") (class "Default")
      (node (ref "Q2") (pin "1") (pinfunction "G_1") (pintype "passive"))
      (node (ref "R16") (pin "1") (pinfunction "1_1") (pintype "passive"))
      (node (ref "R17") (pin "1") (pinfunction "1_1") (pintype "passive"))
    )
    (net (code "80") (name "Net-(Q6-D)") (class "Default")
      (node (ref "Q6") (pin "3") (pinfunction "D_3") (pintype "bidirectional"))
      (node (ref "RGBLEDS") (pin "2") (pinfunction "2_2") (pintype "passive"))
    )
    (net (code "81") (name "Net-(Q7-D)") (class "Default")
      (node (ref "Q7") (pin "3") (pinfunction "D_3") (pintype "bidirectional"))
      (node (ref "RGBLEDS") (pin "3") (pinfunction "3_3") (pintype "passive"))
    )
    (net (code "82") (name "Net-(Q8-D)") (class "Default")
      (node (ref "Q8") (pin "3") (pinfunction "D_3") (pintype "bidirectional"))
      (node (ref "RGBLEDS") (pin "4") (pinfunction "4_4") (pintype "passive"))
    )
    (net (code "83") (name "Net-(R33-Pad1)") (class "Default")
      (node (ref "R33") (pin "1") (pinfunction "1_1") (pintype "passive"))
      (node (ref "TXLED") (pin "A") (pinfunction "A_A") (pintype "passive"))
    )
    (net (code "84") (name "Net-(R34-Pad1)") (class "Default")
      (node (ref "R34") (pin "1") (pinfunction "1_1") (pintype "passive"))
      (node (ref "RXLED") (pin "A") (pinfunction "A_A") (pintype "passive"))
    )
    (net (code "85") (name "Net-(USBB-S1)") (class "Default")
      (node (ref "L4") (pin "1") (pinfunction "1_1") (pintype "passive"))
      (node (ref "USB") (pin "5") (pinfunction "5_5") (pintype "passive"))
      (node (ref "USB") (pin "M1") (pinfunction "S1_M1") (pintype "passive"))
      (node (ref "USB") (pin "M2") (pinfunction "S2_M2") (pintype "passive"))
      (node (ref "USB") (pin "M3") (pinfunction "S3_M3") (pintype "passive"))
      (node (ref "USB") (pin "M4") (pinfunction "S4_M4") (pintype "passive"))
    )
    (net (code "86") (name "unconnected-(ATMEGA2560-(CLKO{slash}ICP3{slash}INT7)_PE7-Pad9)") (class "Default")
      (node (ref "ATMEGA2560") (pin "9") (pinfunction "(CLKO/ICP3/INT7)_PE7_9") (pintype "bidirectional"))
    )
    (net (code "87") (name "unconnected-(ATMEGA2560-(ICP4)_PL0-Pad35)") (class "Default")
      (node (ref "ATMEGA2560") (pin "35") (pinfunction "(ICP4)_PL0_35") (pintype "bidirectional"))
    )
    (net (code "88") (name "unconnected-(ATMEGA2560-(ICP5)_PL1-Pad36)") (class "Default")
      (node (ref "ATMEGA2560") (pin "36") (pinfunction "(ICP5)_PL1_36") (pintype "bidirectional"))
    )
    (net (code "89") (name "unconnected-(ATMEGA2560-(OC2A{slash}PCINT4)_PB4-Pad23)") (class "Default")
      (node (ref "ATMEGA2560") (pin "23") (pinfunction "(OC2A/PCINT4)_PB4_23") (pintype "bidirectional"))
    )
    (net (code "90") (name "unconnected-(ATMEGA2560-(OC5A)_PL3-Pad38)") (class "Default")
      (node (ref "ATMEGA2560") (pin "38") (pinfunction "(OC5A)_PL3_38") (pintype "bidirectional"))
    )
    (net (code "91") (name "unconnected-(ATMEGA2560-(OC5B)_PL4-Pad39)") (class "Default")
      (node (ref "ATMEGA2560") (pin "39") (pinfunction "(OC5B)_PL4_39") (pintype "bidirectional"))
    )
    (net (code "92") (name "unconnected-(ATMEGA2560-(RXD2)_PH0-Pad12)") (class "Default")
      (node (ref "ATMEGA2560") (pin "12") (pinfunction "(RXD2)_PH0_12") (pintype "bidirectional"))
    )
    (net (code "93") (name "unconnected-(ATMEGA2560-(T0)_PD7-Pad50)") (class "Default")
      (node (ref "ATMEGA2560") (pin "50") (pinfunction "(T0)_PD7_50") (pintype "bidirectional"))
    )
    (net (code "94") (name "unconnected-(ATMEGA2560-(T1)_PD6-Pad49)") (class "Default")
      (node (ref "ATMEGA2560") (pin "49") (pinfunction "(T1)_PD6_49") (pintype "bidirectional"))
    )
    (net (code "95") (name "unconnected-(ATMEGA2560-(T3{slash}INT6)_PE6-Pad8)") (class "Default")
      (node (ref "ATMEGA2560") (pin "8") (pinfunction "(T3/INT6)_PE6_8") (pintype "bidirectional"))
    )
    (net (code "96") (name "unconnected-(ATMEGA2560-(T4)_PH7-Pad27)") (class "Default")
      (node (ref "ATMEGA2560") (pin "27") (pinfunction "(T4)_PH7_27") (pintype "bidirectional"))
    )
    (net (code "97") (name "unconnected-(ATMEGA2560-(T5)_PL2-Pad37)") (class "Default")
      (node (ref "ATMEGA2560") (pin "37") (pinfunction "(T5)_PL2_37") (pintype "bidirectional"))
    )
    (net (code "98") (name "unconnected-(ATMEGA2560-(TOSC1)_PG4-Pad29)") (class "Default")
      (node (ref "ATMEGA2560") (pin "29") (pinfunction "(TOSC1)_PG4_29") (pintype "bidirectional"))
    )
    (net (code "99") (name "unconnected-(ATMEGA2560-(TOSC2)_PG3-Pad28)") (class "Default")
      (node (ref "ATMEGA2560") (pin "28") (pinfunction "(TOSC2)_PG3_28") (pintype "bidirectional"))
    )
    (net (code "100") (name "unconnected-(ATMEGA2560-(TXD2)_PH1-Pad13)") (class "Default")
      (node (ref "ATMEGA2560") (pin "13") (pinfunction "(TXD2)_PH1_13") (pintype "bidirectional"))
    )
    (net (code "101") (name "unconnected-(ATMEGA2560-(XCK0{slash}AIN0)_PE2-Pad4)") (class "Default")
      (node (ref "ATMEGA2560") (pin "4") (pinfunction "(XCK0/AIN0)_PE2_4") (pintype "bidirectional"))
    )
    (net (code "102") (name "unconnected-(ATMEGA2560-(XCK1)_PD5-Pad48)") (class "Default")
      (node (ref "ATMEGA2560") (pin "48") (pinfunction "(XCK1)_PD5_48") (pintype "bidirectional"))
    )
    (net (code "103") (name "unconnected-(ATMEGA2560-(XCK2)_PH2-Pad14)") (class "Default")
      (node (ref "ATMEGA2560") (pin "14") (pinfunction "(XCK2)_PH2_14") (pintype "bidirectional"))
    )
    (net (code "104") (name "unconnected-(ATMEGA2560-OC5C)_PL5-Pad40)") (class "Default")
      (node (ref "ATMEGA2560") (pin "40") (pinfunction "OC5C)_PL5_40") (pintype "bidirectional"))
    )
    (net (code "105") (name "unconnected-(ATMEGA2560-PC0_(A8)-Pad53)") (class "Default")
      (node (ref "ATMEGA2560") (pin "53") (pinfunction "PC0_(A8)_53") (pintype "bidirectional"))
    )
    (net (code "106") (name "unconnected-(ATMEGA2560-PC1_(A9)-Pad54)") (class "Default")
      (node (ref "ATMEGA2560") (pin "54") (pinfunction "PC1_(A9)_54") (pintype "bidirectional"))
    )
    (net (code "107") (name "unconnected-(ATMEGA2560-PC2_(A10)-Pad55)") (class "Default")
      (node (ref "ATMEGA2560") (pin "55") (pinfunction "PC2_(A10)_55") (pintype "bidirectional"))
    )
    (net (code "108") (name "unconnected-(ATMEGA2560-PC3_(A11)-Pad56)") (class "Default")
      (node (ref "ATMEGA2560") (pin "56") (pinfunction "PC3_(A11)_56") (pintype "bidirectional"))
    )
    (net (code "109") (name "unconnected-(ATMEGA2560-PC4_(A12)-Pad57)") (class "Default")
      (node (ref "ATMEGA2560") (pin "57") (pinfunction "PC4_(A12)_57") (pintype "bidirectional"))
    )
    (net (code "110") (name "unconnected-(ATMEGA2560-PC5_(A13)-Pad58)") (class "Default")
      (node (ref "ATMEGA2560") (pin "58") (pinfunction "PC5_(A13)_58") (pintype "bidirectional"))
    )
    (net (code "111") (name "unconnected-(ATMEGA2560-PC6_(A14)-Pad59)") (class "Default")
      (node (ref "ATMEGA2560") (pin "59") (pinfunction "PC6_(A14)_59") (pintype "bidirectional"))
    )
    (net (code "112") (name "unconnected-(ATMEGA2560-PC7_(A15)-Pad60)") (class "Default")
      (node (ref "ATMEGA2560") (pin "60") (pinfunction "PC7_(A15)_60") (pintype "bidirectional"))
    )
    (net (code "113") (name "unconnected-(ATMEGA2560-PG0_(~{WR})-Pad51)") (class "Default")
      (node (ref "ATMEGA2560") (pin "51") (pinfunction "PG0_(~{WR})_51") (pintype "bidirectional"))
    )
    (net (code "114") (name "unconnected-(ATMEGA2560-PG1_(~{RD})-Pad52)") (class "Default")
      (node (ref "ATMEGA2560") (pin "52") (pinfunction "PG1_(~{RD})_52") (pintype "bidirectional"))
    )
    (net (code "115") (name "unconnected-(ATMEGA2560-PG2_(ALE)-Pad70)") (class "Default")
      (node (ref "ATMEGA2560") (pin "70") (pinfunction "PG2_(ALE)_70") (pintype "bidirectional"))
    )
    (net (code "116") (name "unconnected-(ATMEGA2560-PJ7-Pad79)") (class "Default")
      (node (ref "ATMEGA2560") (pin "79") (pinfunction "PJ7_79") (pintype "bidirectional"))
    )
    (net (code "117") (name "unconnected-(ATMEGA2560-PK6_(ADC14{slash}PCINT22)-Pad83)") (class "Default")
      (node (ref "ATMEGA2560") (pin "83") (pinfunction "PK6_(ADC14/PCINT22)_83") (pintype "bidirectional"))
    )
    (net (code "118") (name "unconnected-(ATMEGA2560-PK7_(ADC15{slash}PCINT23)-Pad82)") (class "Default")
      (node (ref "ATMEGA2560") (pin "82") (pinfunction "PK7_(ADC15/PCINT23)_82") (pintype "bidirectional"))
    )
    (net (code "119") (name "unconnected-(ATMEGA2560-PL6-Pad41)") (class "Default")
      (node (ref "ATMEGA2560") (pin "41") (pinfunction "PL6_41") (pintype "bidirectional"))
    )
    (net (code "120") (name "unconnected-(ATMEGA2560-PL7-Pad42)") (class "Default")
      (node (ref "ATMEGA2560") (pin "42") (pinfunction "PL7_42") (pintype "bidirectional"))
    )
    (net (code "121") (name "unconnected-(IC2-CBUS2-Pad13)") (class "Default")
      (node (ref "IC2") (pin "13") (pinfunction "CBUS2_13") (pintype "bidirectional"))
    )
    (net (code "122") (name "unconnected-(IC2-CBUS3-Pad14)") (class "Default")
      (node (ref "IC2") (pin "14") (pinfunction "CBUS3_14") (pintype "bidirectional"))
    )
    (net (code "123") (name "unconnected-(IC2-CBUS4-Pad12)") (class "Default")
      (node (ref "IC2") (pin "12") (pinfunction "CBUS4_12") (pintype "bidirectional"))
    )
    (net (code "124") (name "unconnected-(IC2-OSCI-Pad27)") (class "Default")
      (node (ref "IC2") (pin "27") (pinfunction "OSCI_27") (pintype "input"))
    )
    (net (code "125") (name "unconnected-(IC2-OSCO-Pad28)") (class "Default")
      (node (ref "IC2") (pin "28") (pinfunction "OSCO_28") (pintype "output"))
    )
    (net (code "126") (name "unconnected-(IC2-~{CTS}-Pad11)") (class "Default")
      (node (ref "IC2") (pin "11") (pinfunction "~{CTS}_11") (pintype "input"))
    )
    (net (code "127") (name "unconnected-(IC2-~{DCD}-Pad10)") (class "Default")
      (node (ref "IC2") (pin "10") (pinfunction "~{DCD}_10") (pintype "input"))
    )
    (net (code "128") (name "unconnected-(IC2-~{DSR}-Pad9)") (class "Default")
      (node (ref "IC2") (pin "9") (pinfunction "~{DSR}_9") (pintype "input"))
    )
    (net (code "129") (name "unconnected-(IC2-~{DTR}-Pad2)") (class "Default")
      (node (ref "IC2") (pin "2") (pinfunction "~{DTR}_2") (pintype "output"))
    )
    (net (code "130") (name "unconnected-(IC2-~{RI}-Pad6)") (class "Default")
      (node (ref "IC2") (pin "6") (pinfunction "~{RI}_6") (pintype "input"))
    )
    (net (code "131") (name "unconnected-(IC2-~{RTS}-Pad3)") (class "Default")
      (node (ref "IC2") (pin "3") (pinfunction "~{RTS}_3") (pintype "output"))
    )
    (net (code "132") (name "unconnected-(LCD-Pad6)") (class "Default")
      (node (ref "LCD") (pin "6") (pinfunction "6_6") (pintype "passive"))
    )
    (net (code "133") (name "unconnected-(USB-Pad4)") (class "Default")
      (node (ref "USB") (pin "4") (pinfunction "4_4") (pintype "passive"))
    )
  )
)
